# wirelessnode_relay.net
KiCad netlist of a schematic drawn in EAGLE
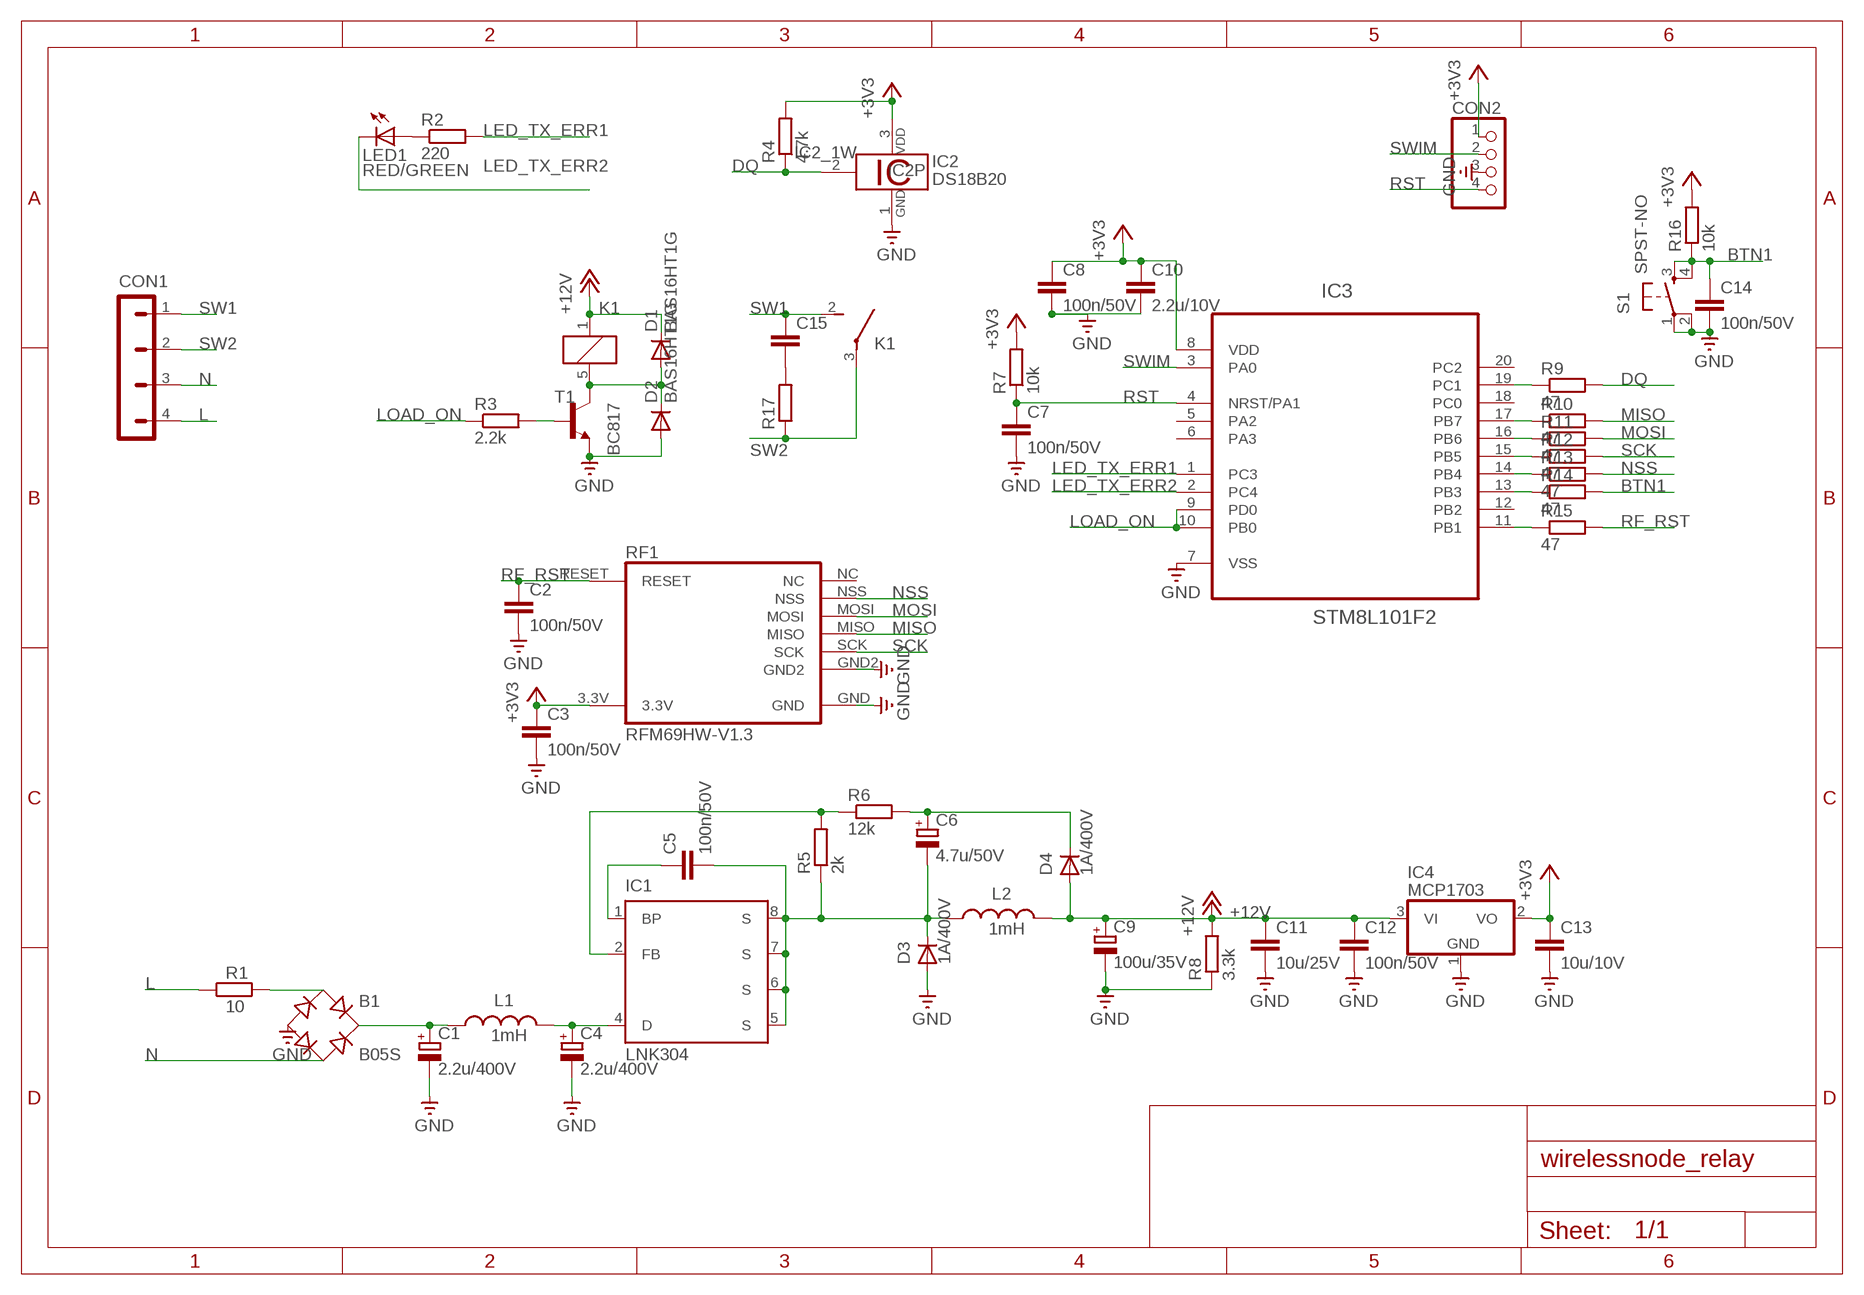
[diagram p0: schematic, sheet 1]

(export (version "E")
  (design (tool "Eeschema 10.0.6"))
  (components
    (comp (ref "B1")
      (value "B05S")
      (footprint "eagle-import:MBS")
      (libsource (lib "eagle-import") (part "BS05"))
    )
    (comp (ref "C1")
      (value "2.2u/400V")
      (footprint "eagle-import:E3.5-8")
      (libsource (lib "eagle-import") (part "C-POL-EUE3.5-8"))
    )
    (comp (ref "C2")
      (value "100n/50V")
      (footprint "eagle-import:C0603K")
      (libsource (lib "eagle-import") (part "C-EUC0603K"))
    )
    (comp (ref "C3")
      (value "100n/50V")
      (footprint "eagle-import:C0603K")
      (libsource (lib "eagle-import") (part "C-EUC0603K"))
    )
    (comp (ref "C4")
      (value "2.2u/400V")
      (footprint "eagle-import:E3.5-8")
      (libsource (lib "eagle-import") (part "C-POL-EUE3.5-8"))
    )
    (comp (ref "C5")
      (value "100n/50V")
      (footprint "eagle-import:C0603K")
      (libsource (lib "eagle-import") (part "C-EUC0603K"))
    )
    (comp (ref "C6")
      (value "4.7u/50V")
      (footprint "eagle-import:PANASONIC_C_LARGER_PADS")
      (libsource (lib "eagle-import") (part "C-POL-EU"))
    )
    (comp (ref "C7")
      (value "100n/50V")
      (footprint "eagle-import:C0603K")
      (libsource (lib "eagle-import") (part "C-EUC0603K"))
    )
    (comp (ref "C8")
      (value "100n/50V")
      (footprint "eagle-import:C0603K")
      (libsource (lib "eagle-import") (part "C-EUC0603K"))
    )
    (comp (ref "C9")
      (value "100u/35V")
      (footprint "eagle-import:PANASONIC_D_LARGER_PADS")
      (libsource (lib "eagle-import") (part "C-POL-EUPANASONIC_D"))
    )
    (comp (ref "C10")
      (value "2.2u/10V")
      (footprint "eagle-import:C0603K")
      (libsource (lib "eagle-import") (part "C-EUC0603K"))
    )
    (comp (ref "C11")
      (value "10u/25V")
      (footprint "eagle-import:C1206")
      (libsource (lib "eagle-import") (part "C-EUC1206"))
    )
    (comp (ref "C12")
      (value "100n/50V")
      (footprint "eagle-import:C0603K")
      (libsource (lib "eagle-import") (part "C-EUC0603K"))
    )
    (comp (ref "C13")
      (value "10u/10V")
      (footprint "eagle-import:C0603K")
      (libsource (lib "eagle-import") (part "C-EUC0603K"))
    )
    (comp (ref "C14")
      (value "100n/50V")
      (footprint "eagle-import:C0603K")
      (libsource (lib "eagle-import") (part "C-EUC0603K"))
    )
    (comp (ref "C15")
      (value "C-EUC1812")
      (footprint "eagle-import:C1812")
      (libsource (lib "eagle-import") (part "C-EUC1812"))
    )
    (comp (ref "CON1")
      (value "POWER_CONN_4")
      (footprint "eagle-import:TERMINAL_BLOCK_4")
      (libsource (lib "eagle-import") (part "POWER_CONN_4"))
    )
    (comp (ref "CON2")
      (value "ZL321-4P")
      (footprint "eagle-import:CON_1X4_1.27_SMD")
      (libsource (lib "eagle-import") (part "CON_1X4PIN_1.27MM_SMD"))
    )
    (comp (ref "D1")
      (value "BAS16HT1G")
      (footprint "eagle-import:SOD323-W")
      (libsource (lib "eagle-import") (part "DIODE-SOD323-W"))
    )
    (comp (ref "D2")
      (value "BAS16HT1G")
      (footprint "eagle-import:SOD323-W")
      (libsource (lib "eagle-import") (part "DIODE-SOD323-W"))
    )
    (comp (ref "D3")
      (value "1A/400V")
      (footprint "eagle-import:DO214-AC")
      (libsource (lib "eagle-import") (part "US1G-DIO"))
    )
    (comp (ref "D4")
      (value "1A/400V")
      (footprint "eagle-import:SOD-123F")
      (libsource (lib "eagle-import") (part "SL1G"))
    )
    (comp (ref "IC1")
      (value "LNK304")
      (footprint "eagle-import:SO8_NO_PIN3")
      (libsource (lib "eagle-import") (part "LNK304"))
    )
    (comp (ref "IC2")
      (value "DS18B20")
      (footprint "eagle-import:TO92-")
      (fields (field (name "TME_ORDER_NUMBER") "DS18B20+"))
      (libsource (lib "eagle-import") (part "DS18B20"))
    )
    (comp (ref "IC3")
      (value "STM8L101F2")
      (footprint "eagle-import:TSSOP20")
      (libsource (lib "eagle-import") (part "STM8L101F2"))
    )
    (comp (ref "IC4")
      (value "MCP1703")
      (footprint "eagle-import:SOT23")
      (libsource (lib "eagle-import") (part "MCP1703CB"))
    )
    (comp (ref "K1")
      (value "G5Q-1A4-EU")
      (footprint "eagle-import:G5Q-1A4-EU")
      (fields (field (name "TME_ORDER_NUMBER") "G5Q-1A4-EU-12DC"))
      (libsource (lib "eagle-import") (part "G5Q-1A4-EU"))
    )
    (comp (ref "L1")
      (value "1mH")
      (footprint "eagle-import:DE0703")
      (libsource (lib "eagle-import") (part "FERROCORE_DE0703-1000"))
    )
    (comp (ref "L2")
      (value "1mH")
      (footprint "eagle-import:DE0703")
      (libsource (lib "eagle-import") (part "FERROCORE_DE0703-1000"))
    )
    (comp (ref "LED1")
      (value "RED/GREEN")
      (footprint "eagle-import:LED5MM")
      (libsource (lib "eagle-import") (part "LED5MM"))
    )
    (comp (ref "R1")
      (value "10")
      (footprint "eagle-import:CF1WS")
      (libsource (lib "eagle-import") (part "R_CF1WS"))
    )
    (comp (ref "R2")
      (value "220")
      (footprint "eagle-import:R0603")
      (libsource (lib "eagle-import") (part "R-EU_R0603"))
    )
    (comp (ref "R3")
      (value "2.2k")
      (footprint "eagle-import:R0603")
      (libsource (lib "eagle-import") (part "R-EU_R0603"))
    )
    (comp (ref "R4")
      (value "4.7k")
      (footprint "eagle-import:R0603")
      (libsource (lib "eagle-import") (part "R-EU_R0603"))
    )
    (comp (ref "R5")
      (value "2k")
      (footprint "eagle-import:R0603")
      (libsource (lib "eagle-import") (part "R-EU_R0603"))
    )
    (comp (ref "R6")
      (value "12k")
      (footprint "eagle-import:R0603")
      (libsource (lib "eagle-import") (part "R-EU_R0603"))
    )
    (comp (ref "R7")
      (value "10k")
      (footprint "eagle-import:R0603")
      (libsource (lib "eagle-import") (part "R-EU_R0603"))
    )
    (comp (ref "R8")
      (value "3.3k")
      (footprint "eagle-import:R0603")
      (libsource (lib "eagle-import") (part "R-EU_R0603"))
    )
    (comp (ref "R9")
      (value "47")
      (footprint "eagle-import:R0603")
      (libsource (lib "eagle-import") (part "R-EU_R0603"))
    )
    (comp (ref "R10")
      (value "47")
      (footprint "eagle-import:R0603")
      (libsource (lib "eagle-import") (part "R-EU_R0603"))
    )
    (comp (ref "R11")
      (value "47")
      (footprint "eagle-import:R0603")
      (libsource (lib "eagle-import") (part "R-EU_R0603"))
    )
    (comp (ref "R12")
      (value "47")
      (footprint "eagle-import:R0603")
      (libsource (lib "eagle-import") (part "R-EU_R0603"))
    )
    (comp (ref "R13")
      (value "47")
      (footprint "eagle-import:R0603")
      (libsource (lib "eagle-import") (part "R-EU_R0603"))
    )
    (comp (ref "R14")
      (value "47")
      (footprint "eagle-import:R0603")
      (libsource (lib "eagle-import") (part "R-EU_R0603"))
    )
    (comp (ref "R15")
      (value "47")
      (footprint "eagle-import:R0603")
      (libsource (lib "eagle-import") (part "R-EU_R0603"))
    )
    (comp (ref "R16")
      (value "10k")
      (footprint "eagle-import:R0603")
      (libsource (lib "eagle-import") (part "R-EU_R0603"))
    )
    (comp (ref "R17")
      (value "R-EU_R2010")
      (footprint "eagle-import:R2010")
      (libsource (lib "eagle-import") (part "R-EU_R2010"))
    )
    (comp (ref "RF1")
      (value "RFM69HW-V1.3")
      (footprint "eagle-import:RFM69HW-V1.3-SMD")
      (libsource (lib "eagle-import") (part "RFM69HW-V1.3"))
    )
    (comp (ref "S1")
      (value "SPST-NO")
      (footprint "eagle-import:DTSM-63X-V-7MM_HEIGHT")
      (libsource (lib "eagle-import") (part "DTSM-63X-V"))
    )
    (comp (ref "T1")
      (value "BC817")
      (footprint "eagle-import:SOT23-BEC")
      (libsource (lib "eagle-import") (part "-NPN-SOT23-BECBC817-16"))
    )
  )
  (nets
    (net (code "1") (name "+3V3") (class "Default")
      (node (ref "C10") (pin "1") (pinfunction "1_1") (pintype "passive"))
      (node (ref "C13") (pin "1") (pinfunction "1_1") (pintype "passive"))
      (node (ref "C3") (pin "1") (pinfunction "1_1") (pintype "passive"))
      (node (ref "C8") (pin "1") (pinfunction "1_1") (pintype "passive"))
      (node (ref "CON2") (pin "1") (pinfunction "1_1") (pintype "passive"))
      (node (ref "IC2") (pin "3") (pinfunction "VDD_3") (pintype "power_in"))
      (node (ref "IC3") (pin "8") (pinfunction "VDD_8") (pintype "power_in"))
      (node (ref "IC4") (pin "2") (pinfunction "VO_2") (pintype "passive"))
      (node (ref "R16") (pin "2") (pinfunction "2_2") (pintype "passive"))
      (node (ref "R4") (pin "2") (pinfunction "2_2") (pintype "passive"))
      (node (ref "R7") (pin "2") (pinfunction "2_2") (pintype "passive"))
      (node (ref "RF1") (pin "3.3V") (pinfunction "3.3V_3.3V") (pintype "power_in"))
    )
    (net (code "2") (name "+12V") (class "Default")
      (node (ref "C11") (pin "1") (pinfunction "1_1") (pintype "passive"))
      (node (ref "C12") (pin "1") (pinfunction "1_1") (pintype "passive"))
      (node (ref "C9") (pin "+") (pinfunction "+_+") (pintype "passive"))
      (node (ref "D1") (pin "C") (pinfunction "C_C") (pintype "passive"))
      (node (ref "D4") (pin "2") (pinfunction "A_2") (pintype "passive"))
      (node (ref "IC4") (pin "3") (pinfunction "VI_3") (pintype "input"))
      (node (ref "K1") (pin "1") (pinfunction "1_1") (pintype "passive"))
      (node (ref "L2") (pin "P$2") (pinfunction "2_P$2") (pintype "passive"))
      (node (ref "R8") (pin "2") (pinfunction "2_2") (pintype "passive"))
    )
    (net (code "3") (name "/BTN1") (class "Default")
      (node (ref "C14") (pin "1") (pinfunction "1_1") (pintype "passive"))
      (node (ref "R14") (pin "2") (pinfunction "2_2") (pintype "passive"))
      (node (ref "R16") (pin "1") (pinfunction "1_1") (pintype "passive"))
      (node (ref "S1") (pin "3") (pinfunction "S_3") (pintype "passive"))
      (node (ref "S1") (pin "4") (pinfunction "S1_4") (pintype "passive"))
    )
    (net (code "4") (name "/DQ") (class "Default")
      (node (ref "IC2") (pin "2") (pinfunction "1W_2") (pintype "power_in"))
      (node (ref "R4") (pin "1") (pinfunction "1_1") (pintype "passive"))
      (node (ref "R9") (pin "2") (pinfunction "2_2") (pintype "passive"))
    )
    (net (code "5") (name "/L") (class "Default")
      (node (ref "CON1") (pin "4") (pinfunction "P$4_4") (pintype "bidirectional"))
      (node (ref "R1") (pin "1") (pinfunction "1_1") (pintype "passive"))
    )
    (net (code "6") (name "/LED_TX_ERR1") (class "Default")
      (node (ref "IC3") (pin "1") (pinfunction "PC3_1") (pintype "bidirectional"))
      (node (ref "R2") (pin "2") (pinfunction "2_2") (pintype "passive"))
    )
    (net (code "7") (name "/LED_TX_ERR2") (class "Default")
      (node (ref "IC3") (pin "2") (pinfunction "PC4_2") (pintype "bidirectional"))
      (node (ref "LED1") (pin "K") (pinfunction "C_K") (pintype "passive"))
    )
    (net (code "8") (name "/LOAD_ON") (class "Default")
      (node (ref "IC3") (pin "10") (pinfunction "PB0_10") (pintype "bidirectional"))
      (node (ref "IC3") (pin "9") (pinfunction "PD0_9") (pintype "bidirectional"))
      (node (ref "R3") (pin "1") (pinfunction "1_1") (pintype "passive"))
    )
    (net (code "9") (name "/MISO") (class "Default")
      (node (ref "R10") (pin "2") (pinfunction "2_2") (pintype "passive"))
      (node (ref "RF1") (pin "MISO") (pinfunction "MISO_MISO") (pintype "output"))
    )
    (net (code "10") (name "/MOSI") (class "Default")
      (node (ref "R11") (pin "2") (pinfunction "2_2") (pintype "passive"))
      (node (ref "RF1") (pin "MOSI") (pinfunction "MOSI_MOSI") (pintype "output"))
    )
    (net (code "11") (name "/N") (class "Default")
      (node (ref "B1") (pin "AC2") (pinfunction "AC2_AC2") (pintype "passive"))
      (node (ref "CON1") (pin "3") (pinfunction "P$3_3") (pintype "bidirectional"))
    )
    (net (code "12") (name "/NSS") (class "Default")
      (node (ref "R13") (pin "2") (pinfunction "2_2") (pintype "passive"))
      (node (ref "RF1") (pin "NSS") (pinfunction "NSS_NSS") (pintype "output"))
    )
    (net (code "13") (name "/RF_RST") (class "Default")
      (node (ref "C2") (pin "1") (pinfunction "1_1") (pintype "passive"))
      (node (ref "R15") (pin "2") (pinfunction "2_2") (pintype "passive"))
      (node (ref "RF1") (pin "RESET") (pinfunction "RESET_RESET") (pintype "power_in"))
    )
    (net (code "14") (name "/RST") (class "Default")
      (node (ref "C7") (pin "1") (pinfunction "1_1") (pintype "passive"))
      (node (ref "CON2") (pin "4") (pinfunction "4_4") (pintype "passive"))
      (node (ref "IC3") (pin "4") (pinfunction "NRST/PA1_4") (pintype "bidirectional"))
      (node (ref "R7") (pin "1") (pinfunction "1_1") (pintype "passive"))
    )
    (net (code "15") (name "/SCK") (class "Default")
      (node (ref "R12") (pin "2") (pinfunction "2_2") (pintype "passive"))
      (node (ref "RF1") (pin "SCK") (pinfunction "SCK_SCK") (pintype "output"))
    )
    (net (code "16") (name "/SW1") (class "Default")
      (node (ref "C15") (pin "1") (pinfunction "1_1") (pintype "passive"))
      (node (ref "CON1") (pin "1") (pinfunction "P$1_1") (pintype "bidirectional"))
      (node (ref "K1") (pin "2") (pinfunction "S_2") (pintype "passive"))
    )
    (net (code "17") (name "/SW2") (class "Default")
      (node (ref "CON1") (pin "2") (pinfunction "P$2_2") (pintype "bidirectional"))
      (node (ref "K1") (pin "3") (pinfunction "P_3") (pintype "passive"))
      (node (ref "R17") (pin "1") (pinfunction "1_1") (pintype "passive"))
    )
    (net (code "18") (name "/SWIM") (class "Default")
      (node (ref "CON2") (pin "2") (pinfunction "2_2") (pintype "passive"))
      (node (ref "IC3") (pin "3") (pinfunction "PA0_3") (pintype "power_in"))
    )
    (net (code "19") (name "GND") (class "Default")
      (node (ref "B1") (pin "-") (pinfunction "-_-") (pintype "passive"))
      (node (ref "C1") (pin "-") (pinfunction "-_-") (pintype "passive"))
      (node (ref "C10") (pin "2") (pinfunction "2_2") (pintype "passive"))
      (node (ref "C11") (pin "2") (pinfunction "2_2") (pintype "passive"))
      (node (ref "C12") (pin "2") (pinfunction "2_2") (pintype "passive"))
      (node (ref "C13") (pin "2") (pinfunction "2_2") (pintype "passive"))
      (node (ref "C14") (pin "2") (pinfunction "2_2") (pintype "passive"))
      (node (ref "C2") (pin "2") (pinfunction "2_2") (pintype "passive"))
      (node (ref "C3") (pin "2") (pinfunction "2_2") (pintype "passive"))
      (node (ref "C4") (pin "-") (pinfunction "-_-") (pintype "passive"))
      (node (ref "C7") (pin "2") (pinfunction "2_2") (pintype "passive"))
      (node (ref "C8") (pin "2") (pinfunction "2_2") (pintype "passive"))
      (node (ref "C9") (pin "-") (pinfunction "-_-") (pintype "passive"))
      (node (ref "CON2") (pin "3") (pinfunction "3_3") (pintype "passive"))
      (node (ref "D2") (pin "A") (pinfunction "A_A") (pintype "passive"))
      (node (ref "D3") (pin "A") (pinfunction "A_A") (pintype "passive"))
      (node (ref "IC2") (pin "1") (pinfunction "GND_1") (pintype "power_in"))
      (node (ref "IC3") (pin "7") (pinfunction "VSS_7") (pintype "power_in"))
      (node (ref "IC4") (pin "1") (pinfunction "GND_1") (pintype "passive"))
      (node (ref "R8") (pin "1") (pinfunction "1_1") (pintype "passive"))
      (node (ref "RF1") (pin "GND") (pinfunction "GND_GND") (pintype "input"))
      (node (ref "RF1") (pin "GND2") (pinfunction "GND2_GND2") (pintype "output"))
      (node (ref "S1") (pin "1") (pinfunction "P_1") (pintype "passive"))
      (node (ref "S1") (pin "2") (pinfunction "P1_2") (pintype "passive"))
      (node (ref "T1") (pin "E") (pinfunction "E_E") (pintype "passive"))
    )
    (net (code "20") (name "Net-(B1-PadAC1)") (class "Default")
      (node (ref "B1") (pin "AC1") (pinfunction "AC1_AC1") (pintype "passive"))
      (node (ref "R1") (pin "2") (pinfunction "2_2") (pintype "passive"))
    )
    (net (code "21") (name "Net-(C15-Pad2)") (class "Default")
      (node (ref "C15") (pin "2") (pinfunction "2_2") (pintype "passive"))
      (node (ref "R17") (pin "2") (pinfunction "2_2") (pintype "passive"))
    )
    (net (code "22") (name "Net-(D4-C)") (class "Default")
      (node (ref "C6") (pin "+") (pinfunction "+_+") (pintype "passive"))
      (node (ref "D4") (pin "1") (pinfunction "C_1") (pintype "passive"))
      (node (ref "R6") (pin "2") (pinfunction "2_2") (pintype "passive"))
    )
    (net (code "23") (name "Net-(IC1-BP)") (class "Default")
      (node (ref "C5") (pin "1") (pinfunction "1_1") (pintype "passive"))
      (node (ref "IC1") (pin "1") (pinfunction "BP_1") (pintype "power_in"))
    )
    (net (code "24") (name "Net-(IC1-D)") (class "Default")
      (node (ref "C4") (pin "+") (pinfunction "+_+") (pintype "passive"))
      (node (ref "IC1") (pin "4") (pinfunction "D_4") (pintype "power_in"))
      (node (ref "L1") (pin "P$2") (pinfunction "2_P$2") (pintype "passive"))
    )
    (net (code "25") (name "Net-(IC1-FB)") (class "Default")
      (node (ref "IC1") (pin "2") (pinfunction "FB_2") (pintype "input"))
      (node (ref "R5") (pin "2") (pinfunction "2_2") (pintype "passive"))
      (node (ref "R6") (pin "1") (pinfunction "1_1") (pintype "passive"))
    )
    (net (code "26") (name "Net-(IC3-PB1)") (class "Default")
      (node (ref "IC3") (pin "11") (pinfunction "PB1_11") (pintype "bidirectional"))
      (node (ref "R15") (pin "1") (pinfunction "1_1") (pintype "passive"))
    )
    (net (code "27") (name "Net-(IC3-PB3)") (class "Default")
      (node (ref "IC3") (pin "13") (pinfunction "PB3_13") (pintype "bidirectional"))
      (node (ref "R14") (pin "1") (pinfunction "1_1") (pintype "passive"))
    )
    (net (code "28") (name "Net-(IC3-PB4)") (class "Default")
      (node (ref "IC3") (pin "14") (pinfunction "PB4_14") (pintype "bidirectional"))
      (node (ref "R13") (pin "1") (pinfunction "1_1") (pintype "passive"))
    )
    (net (code "29") (name "Net-(IC3-PB5)") (class "Default")
      (node (ref "IC3") (pin "15") (pinfunction "PB5_15") (pintype "bidirectional"))
      (node (ref "R12") (pin "1") (pinfunction "1_1") (pintype "passive"))
    )
    (net (code "30") (name "Net-(IC3-PB6)") (class "Default")
      (node (ref "IC3") (pin "16") (pinfunction "PB6_16") (pintype "bidirectional"))
      (node (ref "R11") (pin "1") (pinfunction "1_1") (pintype "passive"))
    )
    (net (code "31") (name "Net-(IC3-PB7)") (class "Default")
      (node (ref "IC3") (pin "17") (pinfunction "PB7_17") (pintype "bidirectional"))
      (node (ref "R10") (pin "1") (pinfunction "1_1") (pintype "passive"))
    )
    (net (code "32") (name "Net-(IC3-PC1)") (class "Default")
      (node (ref "IC3") (pin "19") (pinfunction "PC1_19") (pintype "bidirectional"))
      (node (ref "R9") (pin "1") (pinfunction "1_1") (pintype "passive"))
    )
    (net (code "33") (name "Net-(K1A-2)") (class "Default")
      (node (ref "D1") (pin "A") (pinfunction "A_A") (pintype "passive"))
      (node (ref "D2") (pin "C") (pinfunction "C_C") (pintype "passive"))
      (node (ref "K1") (pin "5") (pinfunction "2_5") (pintype "passive"))
      (node (ref "T1") (pin "C") (pinfunction "C_C") (pintype "passive"))
    )
    (net (code "34") (name "Net-(L1-1)") (class "Default")
      (node (ref "B1") (pin "+") (pinfunction "+_+") (pintype "passive"))
      (node (ref "C1") (pin "+") (pinfunction "+_+") (pintype "passive"))
      (node (ref "L1") (pin "P$1") (pinfunction "1_P$1") (pintype "passive"))
    )
    (net (code "35") (name "Net-(L2-1)") (class "Default")
      (node (ref "C5") (pin "2") (pinfunction "2_2") (pintype "passive"))
      (node (ref "C6") (pin "-") (pinfunction "-_-") (pintype "passive"))
      (node (ref "D3") (pin "C") (pinfunction "C_C") (pintype "passive"))
      (node (ref "IC1") (pin "5") (pinfunction "S_5") (pintype "power_in"))
      (node (ref "IC1") (pin "6") (pinfunction "S_6") (pintype "power_in"))
      (node (ref "IC1") (pin "7") (pinfunction "S_7") (pintype "power_in"))
      (node (ref "IC1") (pin "8") (pinfunction "S_8") (pintype "power_in"))
      (node (ref "L2") (pin "P$1") (pinfunction "1_P$1") (pintype "passive"))
      (node (ref "R5") (pin "1") (pinfunction "1_1") (pintype "passive"))
    )
    (net (code "36") (name "Net-(LED1-PadA)") (class "Default")
      (node (ref "LED1") (pin "A") (pinfunction "A_A") (pintype "passive"))
      (node (ref "R2") (pin "1") (pinfunction "1_1") (pintype "passive"))
    )
    (net (code "37") (name "Net-(R3-Pad2)") (class "Default")
      (node (ref "R3") (pin "2") (pinfunction "2_2") (pintype "passive"))
      (node (ref "T1") (pin "B") (pinfunction "B_B") (pintype "passive"))
    )
    (net (code "38") (name "unconnected-(IC3-PA2-Pad5)") (class "Default")
      (node (ref "IC3") (pin "5") (pinfunction "PA2_5") (pintype "bidirectional"))
    )
    (net (code "39") (name "unconnected-(IC3-PA3-Pad6)") (class "Default")
      (node (ref "IC3") (pin "6") (pinfunction "PA3_6") (pintype "bidirectional"))
    )
    (net (code "40") (name "unconnected-(IC3-PB2-Pad12)") (class "Default")
      (node (ref "IC3") (pin "12") (pinfunction "PB2_12") (pintype "bidirectional"))
    )
    (net (code "41") (name "unconnected-(IC3-PC0-Pad18)") (class "Default")
      (node (ref "IC3") (pin "18") (pinfunction "PC0_18") (pintype "bidirectional"))
    )
    (net (code "42") (name "unconnected-(IC3-PC2-Pad20)") (class "Default")
      (node (ref "IC3") (pin "20") (pinfunction "PC2_20") (pintype "bidirectional"))
    )
    (net (code "43") (name "unconnected-(RF1-PadNC)") (class "Default")
      (node (ref "RF1") (pin "NC") (pinfunction "NC_NC") (pintype "output"))
    )
  )
)
